# CCM_0010.net
KiCad netlist of a schematic drawn in EAGLE
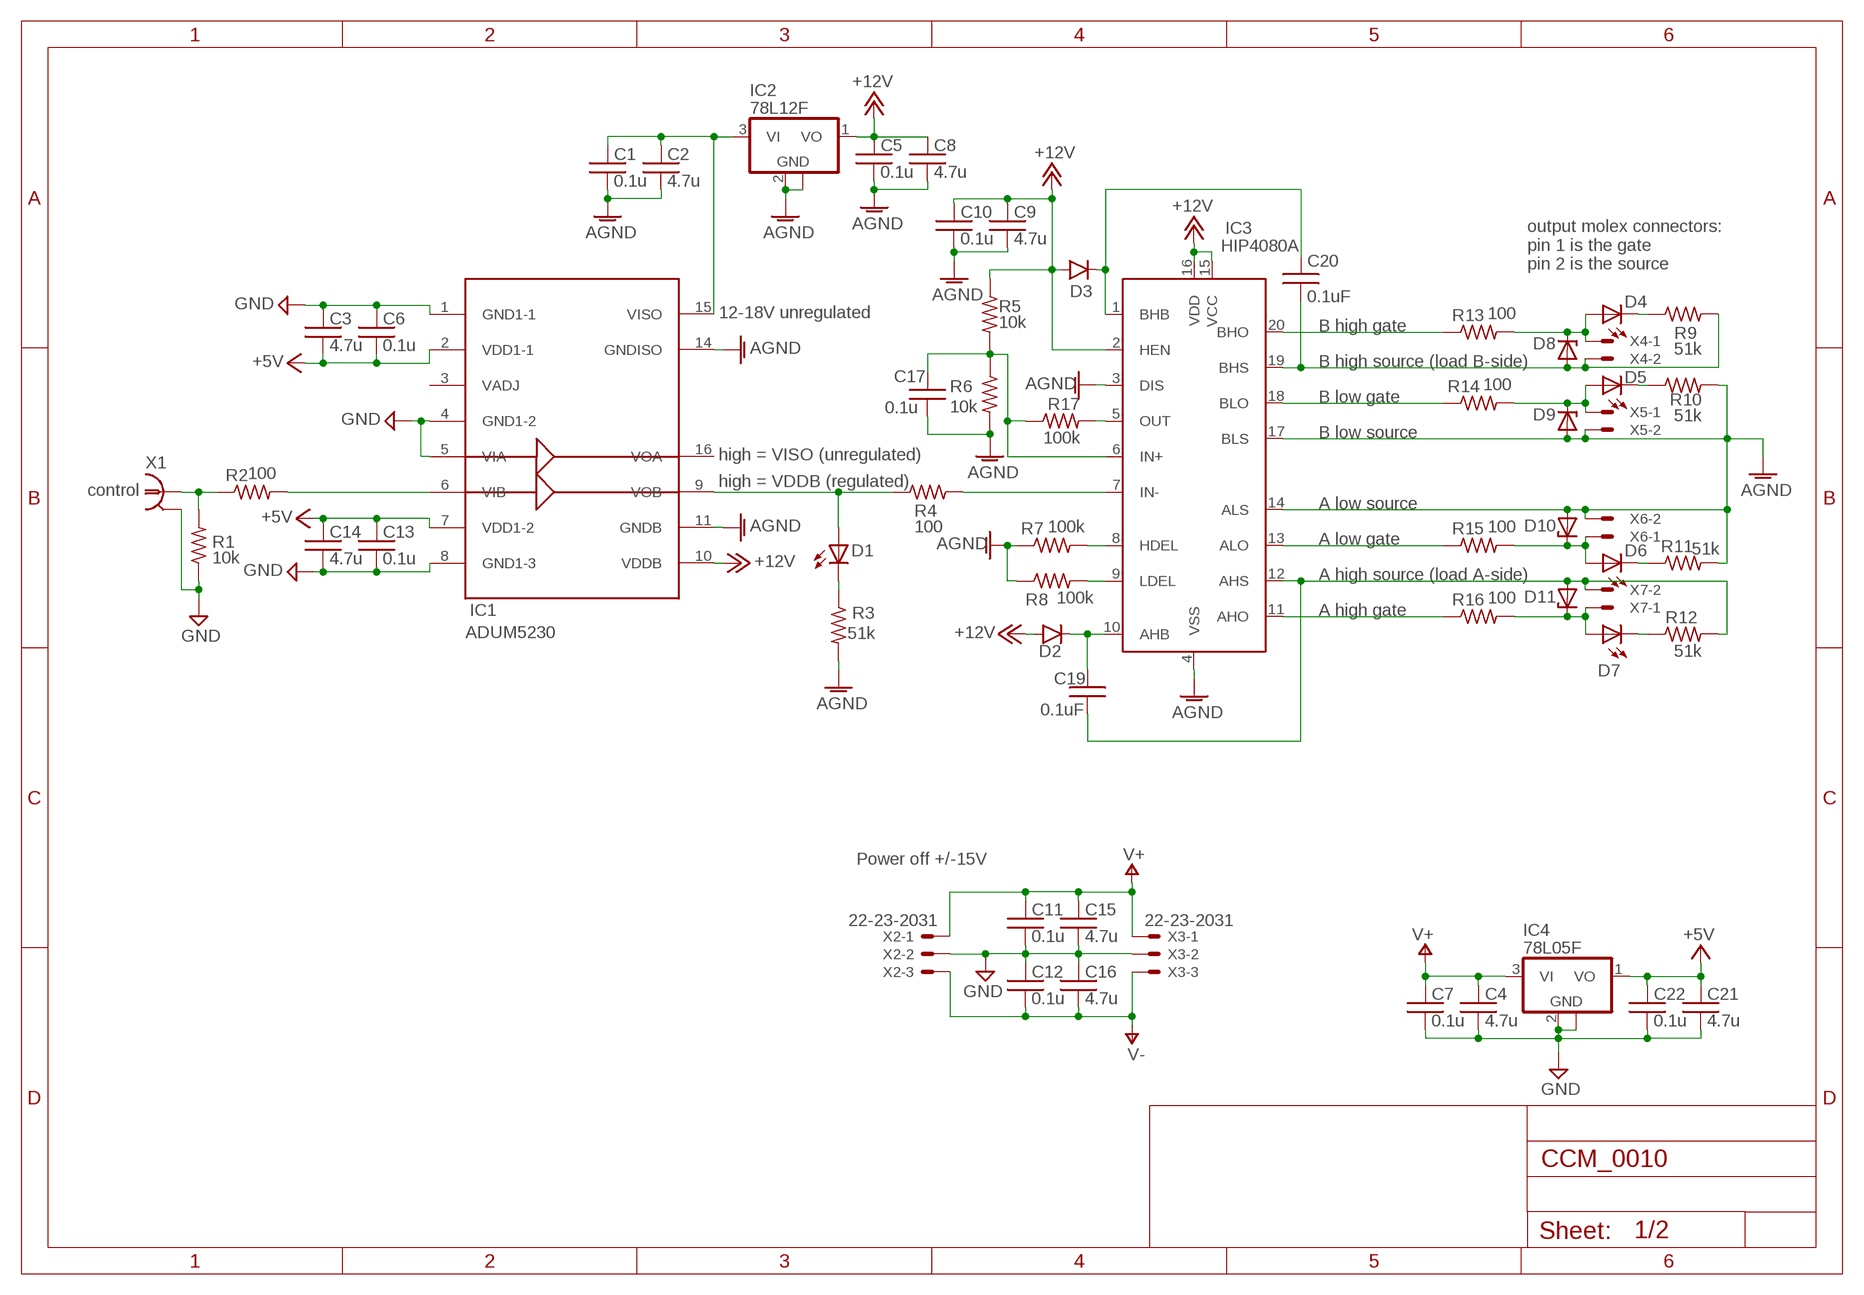
[diagram p0: schematic, sheet 1]
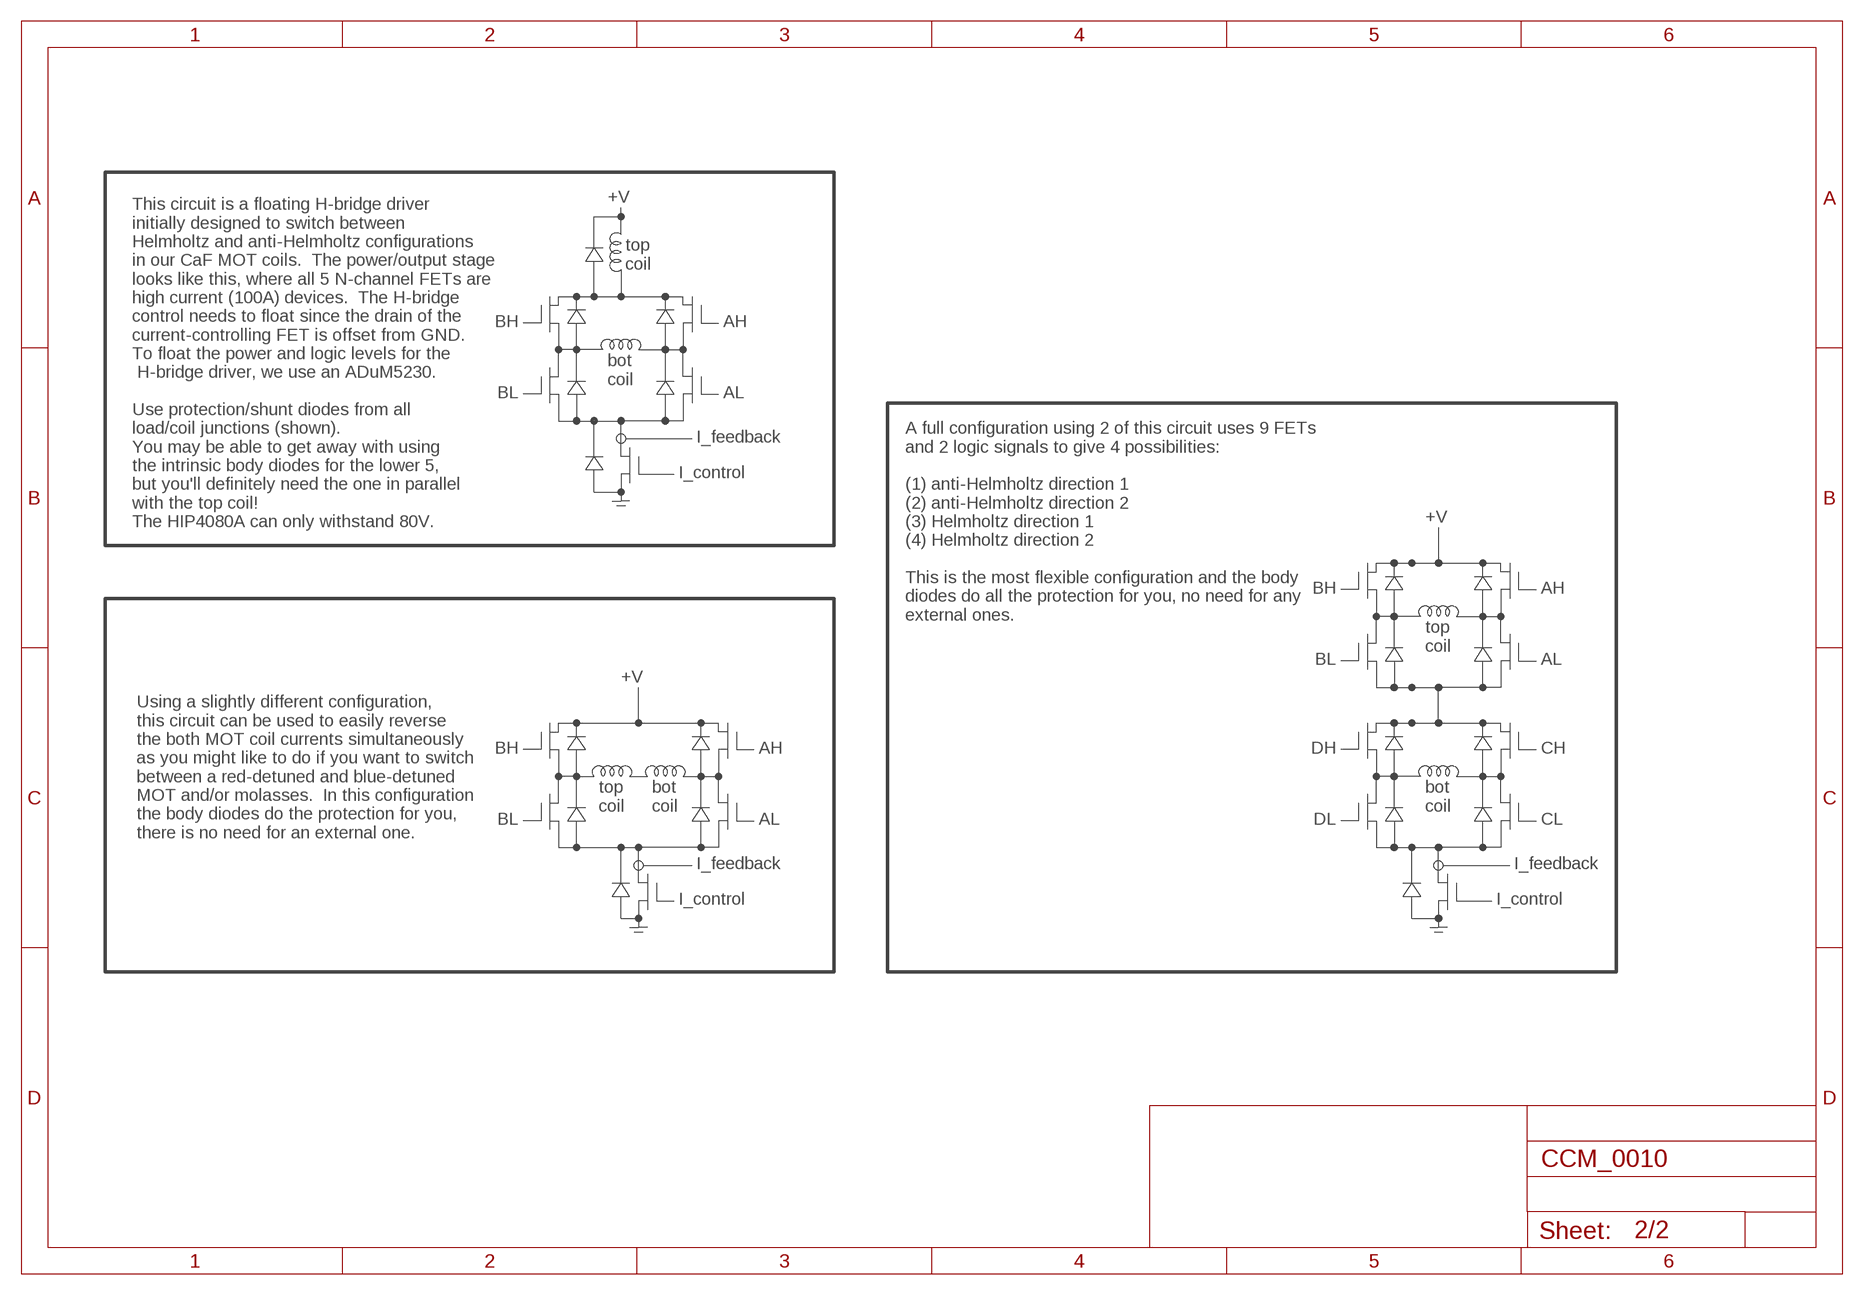
[diagram p1: schematic, sheet 2]

(export (version "E")
  (design (tool "Eeschema 10.0.6"))
  (components
    (comp (ref "C1")
      (value "0.1u")
      (footprint "eagle-import:0603")
      (libsource (lib "eagle-import") (part "C0603"))
    )
    (comp (ref "C2")
      (value "4.7u")
      (footprint "eagle-import:0603")
      (libsource (lib "eagle-import") (part "C0603"))
    )
    (comp (ref "C3")
      (value "4.7u")
      (footprint "eagle-import:0603")
      (libsource (lib "eagle-import") (part "C0603"))
    )
    (comp (ref "C4")
      (value "4.7u")
      (footprint "eagle-import:0603")
      (libsource (lib "eagle-import") (part "C0603"))
    )
    (comp (ref "C5")
      (value "0.1u")
      (footprint "eagle-import:0603")
      (libsource (lib "eagle-import") (part "C0603"))
    )
    (comp (ref "C6")
      (value "0.1u")
      (footprint "eagle-import:0603")
      (libsource (lib "eagle-import") (part "C0603"))
    )
    (comp (ref "C7")
      (value "0.1u")
      (footprint "eagle-import:0603")
      (libsource (lib "eagle-import") (part "C0603"))
    )
    (comp (ref "C8")
      (value "4.7u")
      (footprint "eagle-import:0603")
      (libsource (lib "eagle-import") (part "C0603"))
    )
    (comp (ref "C9")
      (value "4.7u")
      (footprint "eagle-import:0603")
      (libsource (lib "eagle-import") (part "C0603"))
    )
    (comp (ref "C10")
      (value "0.1u")
      (footprint "eagle-import:0603")
      (libsource (lib "eagle-import") (part "C0603"))
    )
    (comp (ref "C11")
      (value "0.1u")
      (footprint "eagle-import:0603")
      (libsource (lib "eagle-import") (part "C0603"))
    )
    (comp (ref "C12")
      (value "0.1u")
      (footprint "eagle-import:0603")
      (libsource (lib "eagle-import") (part "C0603"))
    )
    (comp (ref "C13")
      (value "0.1u")
      (footprint "eagle-import:0603")
      (libsource (lib "eagle-import") (part "C0603"))
    )
    (comp (ref "C14")
      (value "4.7u")
      (footprint "eagle-import:0603")
      (libsource (lib "eagle-import") (part "C0603"))
    )
    (comp (ref "C15")
      (value "4.7u")
      (footprint "eagle-import:0603")
      (libsource (lib "eagle-import") (part "C0603"))
    )
    (comp (ref "C16")
      (value "4.7u")
      (footprint "eagle-import:0603")
      (libsource (lib "eagle-import") (part "C0603"))
    )
    (comp (ref "C17")
      (value "0.1u")
      (footprint "eagle-import:0603")
      (libsource (lib "eagle-import") (part "C0603"))
    )
    (comp (ref "C19")
      (value "0.1uF")
      (footprint "eagle-import:0603")
      (libsource (lib "eagle-import") (part "C0603"))
    )
    (comp (ref "C20")
      (value "0.1uF")
      (footprint "eagle-import:0603")
      (libsource (lib "eagle-import") (part "C0603"))
    )
    (comp (ref "C21")
      (value "4.7u")
      (footprint "eagle-import:0603")
      (libsource (lib "eagle-import") (part "C0603"))
    )
    (comp (ref "C22")
      (value "0.1u")
      (footprint "eagle-import:0603")
      (libsource (lib "eagle-import") (part "C0603"))
    )
    (comp (ref "D1")
      (value "LED0603")
      (footprint "eagle-import:LED0603")
      (libsource (lib "eagle-import") (part "LED0603"))
    )
    (comp (ref "D2")
      (value "DIODESOT23")
      (footprint "eagle-import:SOT23-3")
      (libsource (lib "eagle-import") (part "DIODESOT23"))
    )
    (comp (ref "D3")
      (value "DIODESOT23")
      (footprint "eagle-import:SOT23-3")
      (libsource (lib "eagle-import") (part "DIODESOT23"))
    )
    (comp (ref "D4")
      (value "LED0603")
      (footprint "eagle-import:LED0603")
      (libsource (lib "eagle-import") (part "LED0603"))
    )
    (comp (ref "D5")
      (value "LED0603")
      (footprint "eagle-import:LED0603")
      (libsource (lib "eagle-import") (part "LED0603"))
    )
    (comp (ref "D6")
      (value "LED0603")
      (footprint "eagle-import:LED0603")
      (libsource (lib "eagle-import") (part "LED0603"))
    )
    (comp (ref "D7")
      (value "LED0603")
      (footprint "eagle-import:LED0603")
      (libsource (lib "eagle-import") (part "LED0603"))
    )
    (comp (ref "D8")
      (value "ZENER-DIODESOT23")
      (footprint "eagle-import:SOT23")
      (libsource (lib "eagle-import") (part "ZENER-DIODESOT23"))
    )
    (comp (ref "D9")
      (value "ZENER-DIODESOT23")
      (footprint "eagle-import:SOT23")
      (libsource (lib "eagle-import") (part "ZENER-DIODESOT23"))
    )
    (comp (ref "D10")
      (value "ZENER-DIODESOT23")
      (footprint "eagle-import:SOT23")
      (libsource (lib "eagle-import") (part "ZENER-DIODESOT23"))
    )
    (comp (ref "D11")
      (value "ZENER-DIODESOT23")
      (footprint "eagle-import:SOT23")
      (libsource (lib "eagle-import") (part "ZENER-DIODESOT23"))
    )
    (comp (ref "IC1")
      (value "ADUM5230")
      (footprint "eagle-import:SO16W")
      (libsource (lib "eagle-import") (part "ADUM5230"))
    )
    (comp (ref "IC2")
      (value "78L12F")
      (footprint "eagle-import:SOT89")
      (libsource (lib "eagle-import") (part "78LF12"))
    )
    (comp (ref "IC3")
      (value "HIP4080A")
      (footprint "eagle-import:SO20W")
      (libsource (lib "eagle-import") (part "HIP4080A"))
    )
    (comp (ref "IC4")
      (value "78L05F")
      (footprint "eagle-import:SOT89")
      (libsource (lib "eagle-import") (part "78LF12"))
    )
    (comp (ref "R1")
      (value "10k")
      (footprint "eagle-import:0603")
      (libsource (lib "eagle-import") (part "R0603"))
    )
    (comp (ref "R2")
      (value "100")
      (footprint "eagle-import:0603")
      (libsource (lib "eagle-import") (part "R0603"))
    )
    (comp (ref "R3")
      (value "51k")
      (footprint "eagle-import:0603")
      (libsource (lib "eagle-import") (part "R0603"))
    )
    (comp (ref "R4")
      (value "100")
      (footprint "eagle-import:0603")
      (libsource (lib "eagle-import") (part "R0603"))
    )
    (comp (ref "R5")
      (value "10k")
      (footprint "eagle-import:0603")
      (libsource (lib "eagle-import") (part "R0603"))
    )
    (comp (ref "R6")
      (value "10k")
      (footprint "eagle-import:0603")
      (libsource (lib "eagle-import") (part "R0603"))
    )
    (comp (ref "R7")
      (value "100k")
      (footprint "eagle-import:0603")
      (libsource (lib "eagle-import") (part "R0603"))
    )
    (comp (ref "R8")
      (value "100k")
      (footprint "eagle-import:0603")
      (libsource (lib "eagle-import") (part "R0603"))
    )
    (comp (ref "R9")
      (value "51k")
      (footprint "eagle-import:0603")
      (libsource (lib "eagle-import") (part "R0603"))
    )
    (comp (ref "R10")
      (value "51k")
      (footprint "eagle-import:0603")
      (libsource (lib "eagle-import") (part "R0603"))
    )
    (comp (ref "R11")
      (value "51k")
      (footprint "eagle-import:0603")
      (libsource (lib "eagle-import") (part "R0603"))
    )
    (comp (ref "R12")
      (value "51k")
      (footprint "eagle-import:0603")
      (libsource (lib "eagle-import") (part "R0603"))
    )
    (comp (ref "R13")
      (value "100")
      (footprint "eagle-import:0603")
      (libsource (lib "eagle-import") (part "R0603"))
    )
    (comp (ref "R14")
      (value "100")
      (footprint "eagle-import:0603")
      (libsource (lib "eagle-import") (part "R0603"))
    )
    (comp (ref "R15")
      (value "100")
      (footprint "eagle-import:0603")
      (libsource (lib "eagle-import") (part "R0603"))
    )
    (comp (ref "R16")
      (value "100")
      (footprint "eagle-import:0603")
      (libsource (lib "eagle-import") (part "R0603"))
    )
    (comp (ref "R17")
      (value "100k")
      (footprint "eagle-import:0603")
      (libsource (lib "eagle-import") (part "R0603"))
    )
    (comp (ref "X1")
      (value "1-227161-0")
      (footprint "eagle-import:AMP_227161")
      (fields (field (name "MF") "TYCO ELECTRONICS") (field (name "MPN") "1-227161"))
      (libsource (lib "eagle-import") (part "?2271611--0"))
    )
    (comp (ref "X2")
      (value "22-23-2031")
      (footprint "eagle-import:22-23-2031")
      (fields (field (name "MF") "MOLEX"))
      (libsource (lib "eagle-import") (part "22-23-2031"))
    )
    (comp (ref "X3")
      (value "22-23-2031")
      (footprint "eagle-import:22-23-2031")
      (fields (field (name "MF") "MOLEX"))
      (libsource (lib "eagle-import") (part "22-23-2031"))
    )
    (comp (ref "X4")
      (value "22-23-2021")
      (footprint "eagle-import:22-23-2021")
      (fields (field (name "MF") "MOLEX"))
      (libsource (lib "eagle-import") (part "22-23-2021"))
    )
    (comp (ref "X5")
      (value "22-23-2021")
      (footprint "eagle-import:22-23-2021")
      (fields (field (name "MF") "MOLEX"))
      (libsource (lib "eagle-import") (part "22-23-2021"))
    )
    (comp (ref "X6")
      (value "22-23-2021")
      (footprint "eagle-import:22-23-2021")
      (fields (field (name "MF") "MOLEX"))
      (libsource (lib "eagle-import") (part "22-23-2021"))
    )
    (comp (ref "X7")
      (value "22-23-2021")
      (footprint "eagle-import:22-23-2021")
      (fields (field (name "MF") "MOLEX"))
      (libsource (lib "eagle-import") (part "22-23-2021"))
    )
  )
  (nets
    (net (code "1") (name "+5V") (class "Default")
      (node (ref "C13") (pin "1") (pinfunction "1_1") (pintype "passive"))
      (node (ref "C14") (pin "1") (pinfunction "1_1") (pintype "passive"))
      (node (ref "C21") (pin "1") (pinfunction "1_1") (pintype "passive"))
      (node (ref "C22") (pin "1") (pinfunction "1_1") (pintype "passive"))
      (node (ref "C3") (pin "2") (pinfunction "2_2") (pintype "passive"))
      (node (ref "C6") (pin "2") (pinfunction "2_2") (pintype "passive"))
      (node (ref "IC1") (pin "2") (pinfunction "VDD1-1_2") (pintype "bidirectional"))
      (node (ref "IC1") (pin "7") (pinfunction "VDD1-2_7") (pintype "bidirectional"))
      (node (ref "IC4") (pin "1") (pinfunction "VO_1") (pintype "passive"))
    )
    (net (code "2") (name "+12V") (class "Default")
      (node (ref "C10") (pin "1") (pinfunction "1_1") (pintype "passive"))
      (node (ref "C5") (pin "1") (pinfunction "1_1") (pintype "passive"))
      (node (ref "C8") (pin "1") (pinfunction "1_1") (pintype "passive"))
      (node (ref "C9") (pin "1") (pinfunction "1_1") (pintype "passive"))
      (node (ref "D2") (pin "1") (pinfunction "A_1") (pintype "passive"))
      (node (ref "D3") (pin "1") (pinfunction "A_1") (pintype "passive"))
      (node (ref "IC1") (pin "10") (pinfunction "VDDB_10") (pintype "bidirectional"))
      (node (ref "IC2") (pin "1") (pinfunction "VO_1") (pintype "passive"))
      (node (ref "IC3") (pin "15") (pinfunction "VCC_15") (pintype "input"))
      (node (ref "IC3") (pin "16") (pinfunction "VDD_16") (pintype "power_in"))
      (node (ref "IC3") (pin "2") (pinfunction "HEN_2") (pintype "input"))
      (node (ref "R5") (pin "1") (pinfunction "1_1") (pintype "passive"))
    )
    (net (code "3") (name "AGND") (class "Default")
      (node (ref "C1") (pin "2") (pinfunction "2_2") (pintype "passive"))
      (node (ref "C10") (pin "2") (pinfunction "2_2") (pintype "passive"))
      (node (ref "C17") (pin "2") (pinfunction "2_2") (pintype "passive"))
      (node (ref "C2") (pin "2") (pinfunction "2_2") (pintype "passive"))
      (node (ref "C5") (pin "2") (pinfunction "2_2") (pintype "passive"))
      (node (ref "C8") (pin "2") (pinfunction "2_2") (pintype "passive"))
      (node (ref "C9") (pin "2") (pinfunction "2_2") (pintype "passive"))
      (node (ref "D10") (pin "1") (pinfunction "A_1") (pintype "passive"))
      (node (ref "D9") (pin "1") (pinfunction "A_1") (pintype "passive"))
      (node (ref "IC1") (pin "11") (pinfunction "GNDB_11") (pintype "bidirectional"))
      (node (ref "IC1") (pin "14") (pinfunction "GNDISO_14") (pintype "bidirectional"))
      (node (ref "IC2") (pin "2") (pinfunction "GND_2") (pintype "passive"))
      (node (ref "IC2") (pin "2@1") (pinfunction "GND_2@1") (pintype "passive"))
      (node (ref "IC3") (pin "14") (pinfunction "ALS_14") (pintype "passive"))
      (node (ref "IC3") (pin "17") (pinfunction "BLS_17") (pintype "passive"))
      (node (ref "IC3") (pin "3") (pinfunction "DIS_3") (pintype "input"))
      (node (ref "IC3") (pin "4") (pinfunction "VSS_4") (pintype "power_in"))
      (node (ref "R10") (pin "2") (pinfunction "2_2") (pintype "passive"))
      (node (ref "R11") (pin "2") (pinfunction "2_2") (pintype "passive"))
      (node (ref "R3") (pin "2") (pinfunction "2_2") (pintype "passive"))
      (node (ref "R6") (pin "2") (pinfunction "2_2") (pintype "passive"))
      (node (ref "R7") (pin "1") (pinfunction "1_1") (pintype "passive"))
      (node (ref "R8") (pin "1") (pinfunction "1_1") (pintype "passive"))
      (node (ref "X5") (pin "2") (pinfunction "S_2") (pintype "passive"))
      (node (ref "X6") (pin "2") (pinfunction "S_2") (pintype "passive"))
    )
    (net (code "4") (name "GND") (class "Default")
      (node (ref "C11") (pin "2") (pinfunction "2_2") (pintype "passive"))
      (node (ref "C12") (pin "1") (pinfunction "1_1") (pintype "passive"))
      (node (ref "C13") (pin "2") (pinfunction "2_2") (pintype "passive"))
      (node (ref "C14") (pin "2") (pinfunction "2_2") (pintype "passive"))
      (node (ref "C15") (pin "2") (pinfunction "2_2") (pintype "passive"))
      (node (ref "C16") (pin "1") (pinfunction "1_1") (pintype "passive"))
      (node (ref "C21") (pin "2") (pinfunction "2_2") (pintype "passive"))
      (node (ref "C22") (pin "2") (pinfunction "2_2") (pintype "passive"))
      (node (ref "C3") (pin "1") (pinfunction "1_1") (pintype "passive"))
      (node (ref "C4") (pin "2") (pinfunction "2_2") (pintype "passive"))
      (node (ref "C6") (pin "1") (pinfunction "1_1") (pintype "passive"))
      (node (ref "C7") (pin "2") (pinfunction "2_2") (pintype "passive"))
      (node (ref "IC1") (pin "1") (pinfunction "GND1-1_1") (pintype "bidirectional"))
      (node (ref "IC1") (pin "4") (pinfunction "GND1-2_4") (pintype "bidirectional"))
      (node (ref "IC1") (pin "5") (pinfunction "VIA_5") (pintype "bidirectional"))
      (node (ref "IC1") (pin "8") (pinfunction "GND1-3_8") (pintype "bidirectional"))
      (node (ref "IC4") (pin "2") (pinfunction "GND_2") (pintype "passive"))
      (node (ref "IC4") (pin "2@1") (pinfunction "GND_2@1") (pintype "passive"))
      (node (ref "R1") (pin "1") (pinfunction "1_1") (pintype "passive"))
      (node (ref "X1") (pin "2") (pinfunction "2_2") (pintype "passive"))
      (node (ref "X2") (pin "2") (pinfunction "S_2") (pintype "passive"))
      (node (ref "X3") (pin "2") (pinfunction "S_2") (pintype "passive"))
    )
    (net (code "5") (name "Net-(D1-PadC)") (class "Default")
      (node (ref "D1") (pin "C") (pinfunction "C_C") (pintype "passive"))
      (node (ref "R3") (pin "1") (pinfunction "1_1") (pintype "passive"))
    )
    (net (code "6") (name "Net-(D2-C)") (class "Default")
      (node (ref "C19") (pin "2") (pinfunction "2_2") (pintype "passive"))
      (node (ref "D2") (pin "3") (pinfunction "C_3") (pintype "passive"))
      (node (ref "IC3") (pin "10") (pinfunction "AHB_10") (pintype "input"))
    )
    (net (code "7") (name "Net-(D3-C)") (class "Default")
      (node (ref "C20") (pin "2") (pinfunction "2_2") (pintype "passive"))
      (node (ref "D3") (pin "3") (pinfunction "C_3") (pintype "passive"))
      (node (ref "IC3") (pin "1") (pinfunction "BHB_1") (pintype "input"))
    )
    (net (code "8") (name "Net-(D4-PadC)") (class "Default")
      (node (ref "D4") (pin "C") (pinfunction "C_C") (pintype "passive"))
      (node (ref "R9") (pin "1") (pinfunction "1_1") (pintype "passive"))
    )
    (net (code "9") (name "Net-(D5-PadC)") (class "Default")
      (node (ref "D5") (pin "C") (pinfunction "C_C") (pintype "passive"))
      (node (ref "R10") (pin "1") (pinfunction "1_1") (pintype "passive"))
    )
    (net (code "10") (name "Net-(D6-PadC)") (class "Default")
      (node (ref "D6") (pin "C") (pinfunction "C_C") (pintype "passive"))
      (node (ref "R11") (pin "1") (pinfunction "1_1") (pintype "passive"))
    )
    (net (code "11") (name "Net-(D7-PadC)") (class "Default")
      (node (ref "D7") (pin "C") (pinfunction "C_C") (pintype "passive"))
      (node (ref "R12") (pin "1") (pinfunction "1_1") (pintype "passive"))
    )
    (net (code "12") (name "Net-(D8-A)") (class "Default")
      (node (ref "C20") (pin "1") (pinfunction "1_1") (pintype "passive"))
      (node (ref "D8") (pin "1") (pinfunction "A_1") (pintype "passive"))
      (node (ref "IC3") (pin "19") (pinfunction "BHS_19") (pintype "input"))
      (node (ref "R9") (pin "2") (pinfunction "2_2") (pintype "passive"))
      (node (ref "X4") (pin "2") (pinfunction "S_2") (pintype "passive"))
    )
    (net (code "13") (name "Net-(D8-C)") (class "Default")
      (node (ref "D4") (pin "A") (pinfunction "A_A") (pintype "passive"))
      (node (ref "D8") (pin "3") (pinfunction "C_3") (pintype "passive"))
      (node (ref "R13") (pin "2") (pinfunction "2_2") (pintype "passive"))
      (node (ref "X4") (pin "1") (pinfunction "S_1") (pintype "passive"))
    )
    (net (code "14") (name "Net-(D9-C)") (class "Default")
      (node (ref "D5") (pin "A") (pinfunction "A_A") (pintype "passive"))
      (node (ref "D9") (pin "3") (pinfunction "C_3") (pintype "passive"))
      (node (ref "R14") (pin "2") (pinfunction "2_2") (pintype "passive"))
      (node (ref "X5") (pin "1") (pinfunction "S_1") (pintype "passive"))
    )
    (net (code "15") (name "Net-(D10-C)") (class "Default")
      (node (ref "D10") (pin "3") (pinfunction "C_3") (pintype "passive"))
      (node (ref "D6") (pin "A") (pinfunction "A_A") (pintype "passive"))
      (node (ref "R15") (pin "2") (pinfunction "2_2") (pintype "passive"))
      (node (ref "X6") (pin "1") (pinfunction "S_1") (pintype "passive"))
    )
    (net (code "16") (name "Net-(D11-A)") (class "Default")
      (node (ref "C19") (pin "1") (pinfunction "1_1") (pintype "passive"))
      (node (ref "D11") (pin "1") (pinfunction "A_1") (pintype "passive"))
      (node (ref "IC3") (pin "12") (pinfunction "AHS_12") (pintype "input"))
      (node (ref "R12") (pin "2") (pinfunction "2_2") (pintype "passive"))
      (node (ref "X7") (pin "2") (pinfunction "S_2") (pintype "passive"))
    )
    (net (code "17") (name "Net-(D11-C)") (class "Default")
      (node (ref "D11") (pin "3") (pinfunction "C_3") (pintype "passive"))
      (node (ref "D7") (pin "A") (pinfunction "A_A") (pintype "passive"))
      (node (ref "R16") (pin "2") (pinfunction "2_2") (pintype "passive"))
      (node (ref "X7") (pin "1") (pinfunction "S_1") (pintype "passive"))
    )
    (net (code "18") (name "Net-(IC1-VIB)") (class "Default")
      (node (ref "IC1") (pin "6") (pinfunction "VIB_6") (pintype "bidirectional"))
      (node (ref "R2") (pin "2") (pinfunction "2_2") (pintype "passive"))
    )
    (net (code "19") (name "Net-(IC1-VISO)") (class "Default")
      (node (ref "C1") (pin "1") (pinfunction "1_1") (pintype "passive"))
      (node (ref "C2") (pin "1") (pinfunction "1_1") (pintype "passive"))
      (node (ref "IC1") (pin "15") (pinfunction "VISO_15") (pintype "bidirectional"))
      (node (ref "IC2") (pin "3") (pinfunction "VI_3") (pintype "input"))
    )
    (net (code "20") (name "Net-(IC1-VOB)") (class "Default")
      (node (ref "D1") (pin "A") (pinfunction "A_A") (pintype "passive"))
      (node (ref "IC1") (pin "9") (pinfunction "VOB_9") (pintype "bidirectional"))
      (node (ref "R4") (pin "1") (pinfunction "1_1") (pintype "passive"))
    )
    (net (code "21") (name "Net-(IC3-AHO)") (class "Default")
      (node (ref "IC3") (pin "11") (pinfunction "AHO_11") (pintype "output"))
      (node (ref "R16") (pin "1") (pinfunction "1_1") (pintype "passive"))
    )
    (net (code "22") (name "Net-(IC3-ALO)") (class "Default")
      (node (ref "IC3") (pin "13") (pinfunction "ALO_13") (pintype "output"))
      (node (ref "R15") (pin "1") (pinfunction "1_1") (pintype "passive"))
    )
    (net (code "23") (name "Net-(IC3-BHO)") (class "Default")
      (node (ref "IC3") (pin "20") (pinfunction "BHO_20") (pintype "output"))
      (node (ref "R13") (pin "1") (pinfunction "1_1") (pintype "passive"))
    )
    (net (code "24") (name "Net-(IC3-BLO)") (class "Default")
      (node (ref "IC3") (pin "18") (pinfunction "BLO_18") (pintype "output"))
      (node (ref "R14") (pin "1") (pinfunction "1_1") (pintype "passive"))
    )
    (net (code "25") (name "Net-(IC3-HDEL)") (class "Default")
      (node (ref "IC3") (pin "8") (pinfunction "HDEL_8") (pintype "input"))
      (node (ref "R7") (pin "2") (pinfunction "2_2") (pintype "passive"))
    )
    (net (code "26") (name "Net-(IC3-IN+)") (class "Default")
      (node (ref "C17") (pin "1") (pinfunction "1_1") (pintype "passive"))
      (node (ref "IC3") (pin "6") (pinfunction "IN+_6") (pintype "input"))
      (node (ref "R17") (pin "1") (pinfunction "1_1") (pintype "passive"))
      (node (ref "R5") (pin "2") (pinfunction "2_2") (pintype "passive"))
      (node (ref "R6") (pin "1") (pinfunction "1_1") (pintype "passive"))
    )
    (net (code "27") (name "Net-(IC3-IN-)") (class "Default")
      (node (ref "IC3") (pin "7") (pinfunction "IN-_7") (pintype "input"))
      (node (ref "R4") (pin "2") (pinfunction "2_2") (pintype "passive"))
    )
    (net (code "28") (name "Net-(IC3-LDEL)") (class "Default")
      (node (ref "IC3") (pin "9") (pinfunction "LDEL_9") (pintype "input"))
      (node (ref "R8") (pin "2") (pinfunction "2_2") (pintype "passive"))
    )
    (net (code "29") (name "Net-(IC3-OUT)") (class "Default")
      (node (ref "IC3") (pin "5") (pinfunction "OUT_5") (pintype "input"))
      (node (ref "R17") (pin "2") (pinfunction "2_2") (pintype "passive"))
    )
    (net (code "30") (name "Net-(R1-Pad2)") (class "Default")
      (node (ref "R1") (pin "2") (pinfunction "2_2") (pintype "passive"))
      (node (ref "R2") (pin "1") (pinfunction "1_1") (pintype "passive"))
      (node (ref "X1") (pin "1") (pinfunction "1_1") (pintype "passive"))
    )
    (net (code "31") (name "V+") (class "Default")
      (node (ref "C11") (pin "1") (pinfunction "1_1") (pintype "passive"))
      (node (ref "C15") (pin "1") (pinfunction "1_1") (pintype "passive"))
      (node (ref "C4") (pin "1") (pinfunction "1_1") (pintype "passive"))
      (node (ref "C7") (pin "1") (pinfunction "1_1") (pintype "passive"))
      (node (ref "IC4") (pin "3") (pinfunction "VI_3") (pintype "input"))
      (node (ref "X2") (pin "1") (pinfunction "S_1") (pintype "passive"))
      (node (ref "X3") (pin "1") (pinfunction "S_1") (pintype "passive"))
    )
    (net (code "32") (name "V-") (class "Default")
      (node (ref "C12") (pin "2") (pinfunction "2_2") (pintype "passive"))
      (node (ref "C16") (pin "2") (pinfunction "2_2") (pintype "passive"))
      (node (ref "X2") (pin "3") (pinfunction "S_3") (pintype "passive"))
      (node (ref "X3") (pin "3") (pinfunction "S_3") (pintype "passive"))
    )
    (net (code "33") (name "unconnected-(IC1-VADJ-Pad3)") (class "Default")
      (node (ref "IC1") (pin "3") (pinfunction "VADJ_3") (pintype "bidirectional"))
    )
    (net (code "34") (name "unconnected-(IC1-VOA-Pad16)") (class "Default")
      (node (ref "IC1") (pin "16") (pinfunction "VOA_16") (pintype "bidirectional"))
    )
  )
)
